# HDMI.net
KiCad netlist of a schematic drawn in Altium Designer
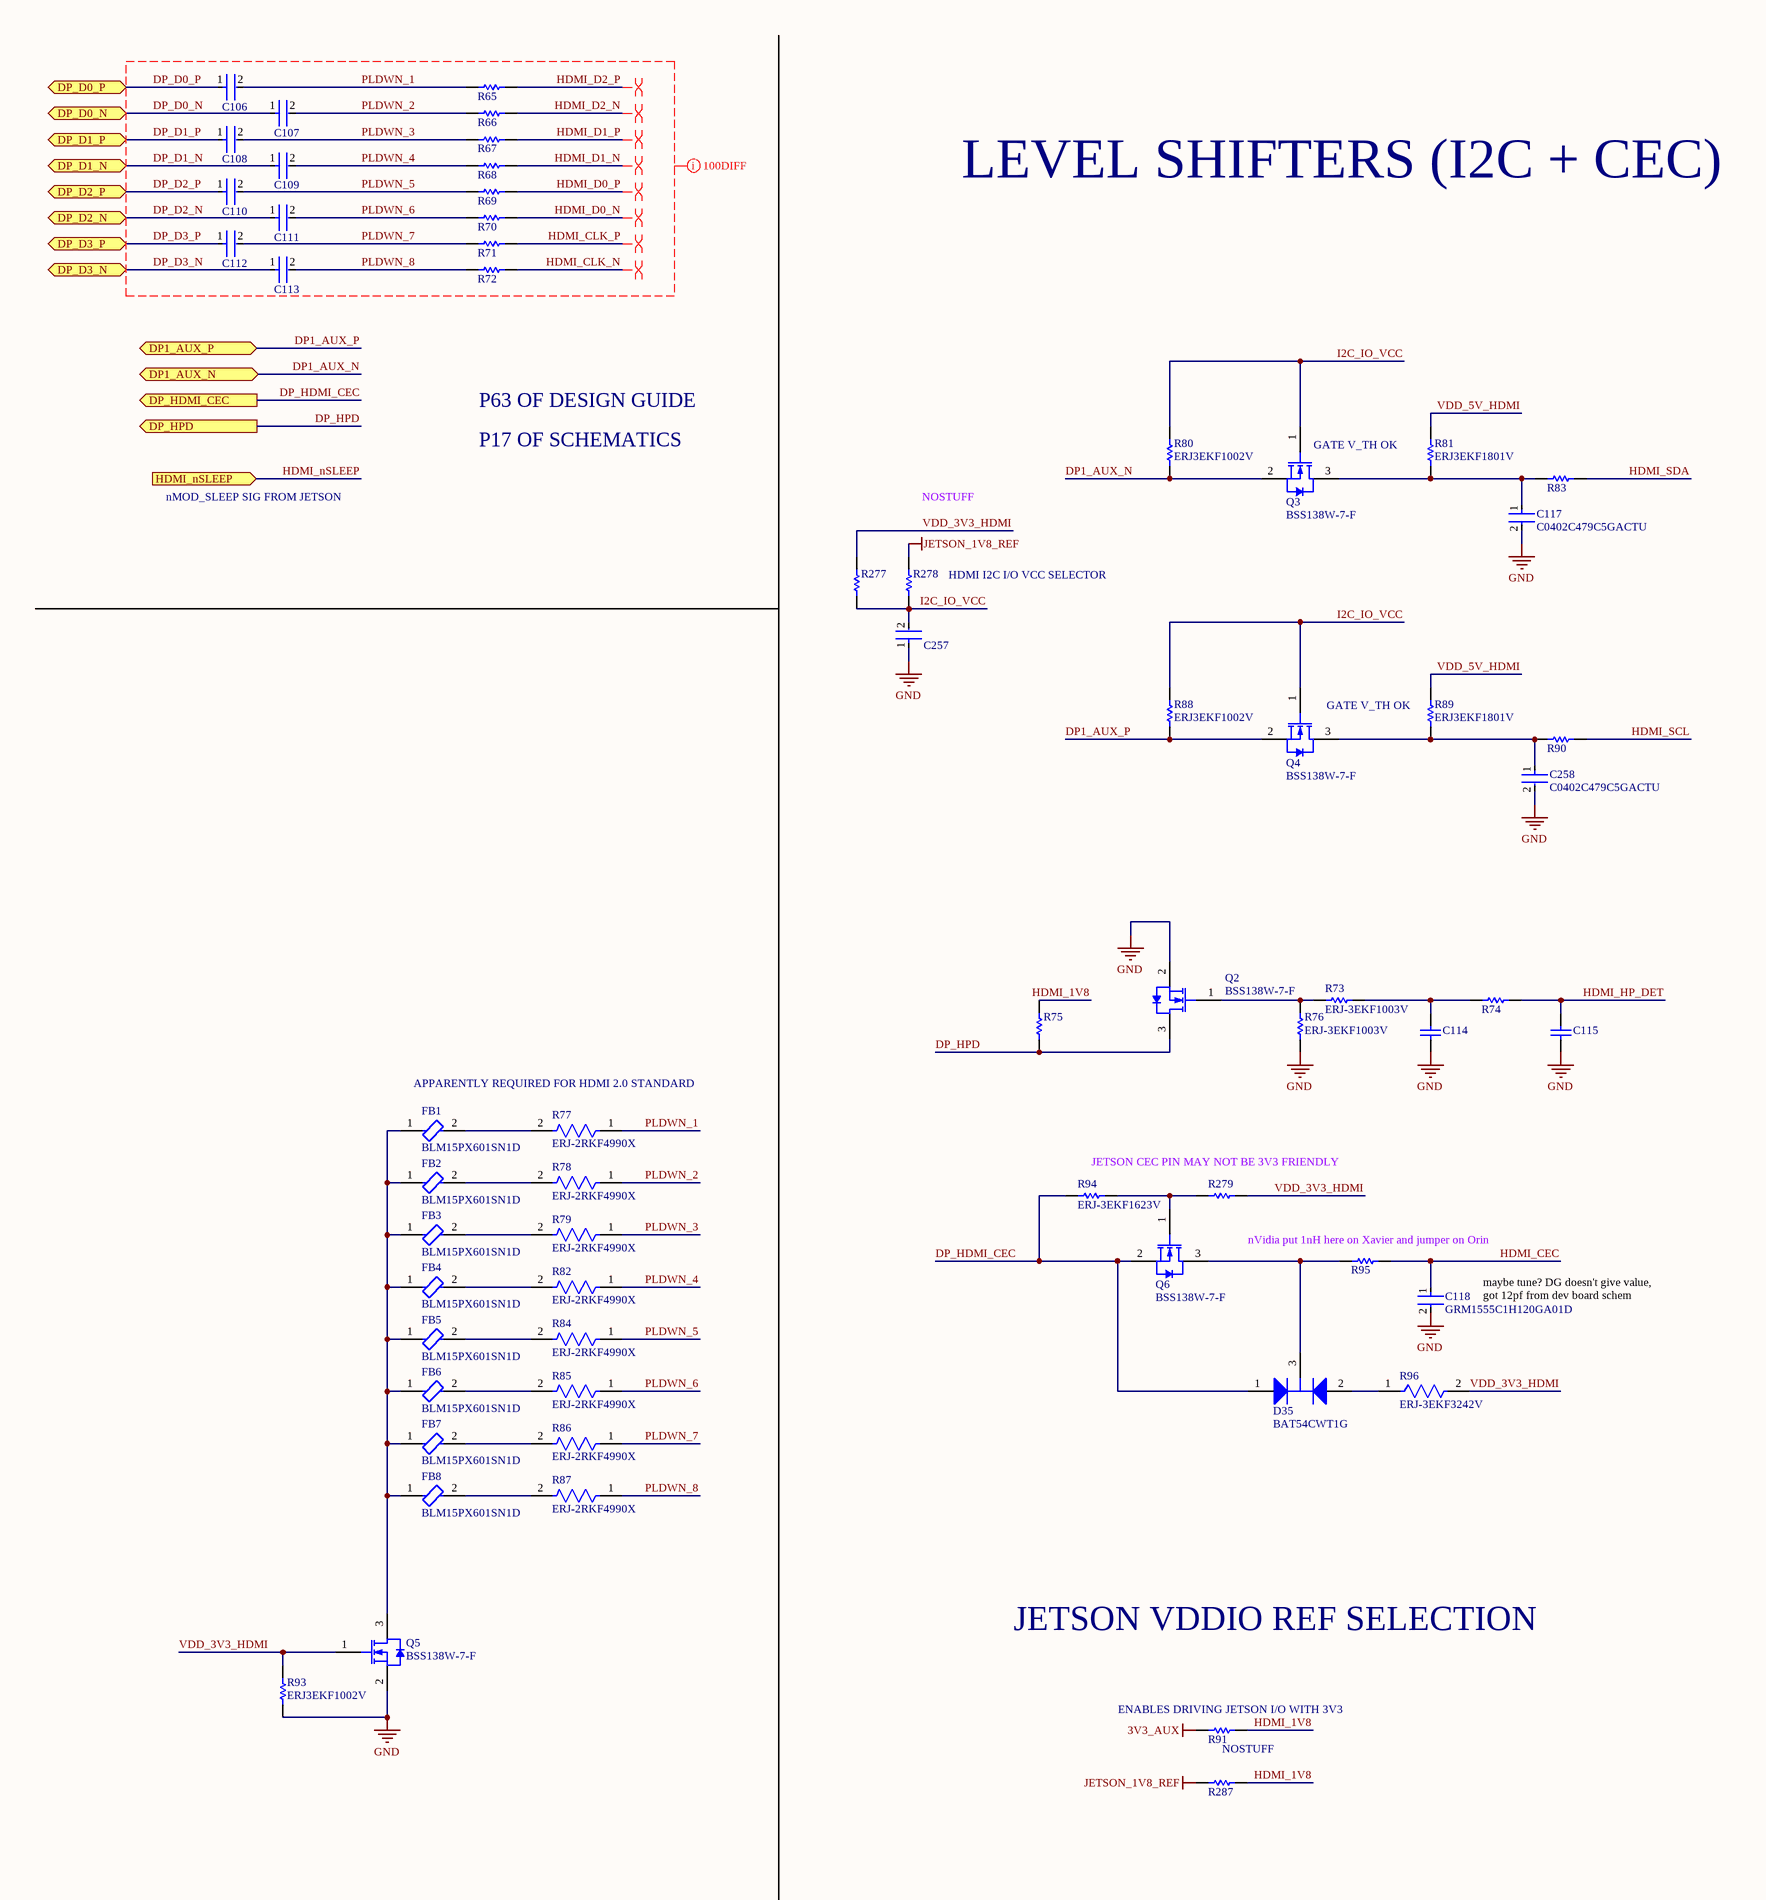
[diagram p0: HDMI.SchDoc, left]
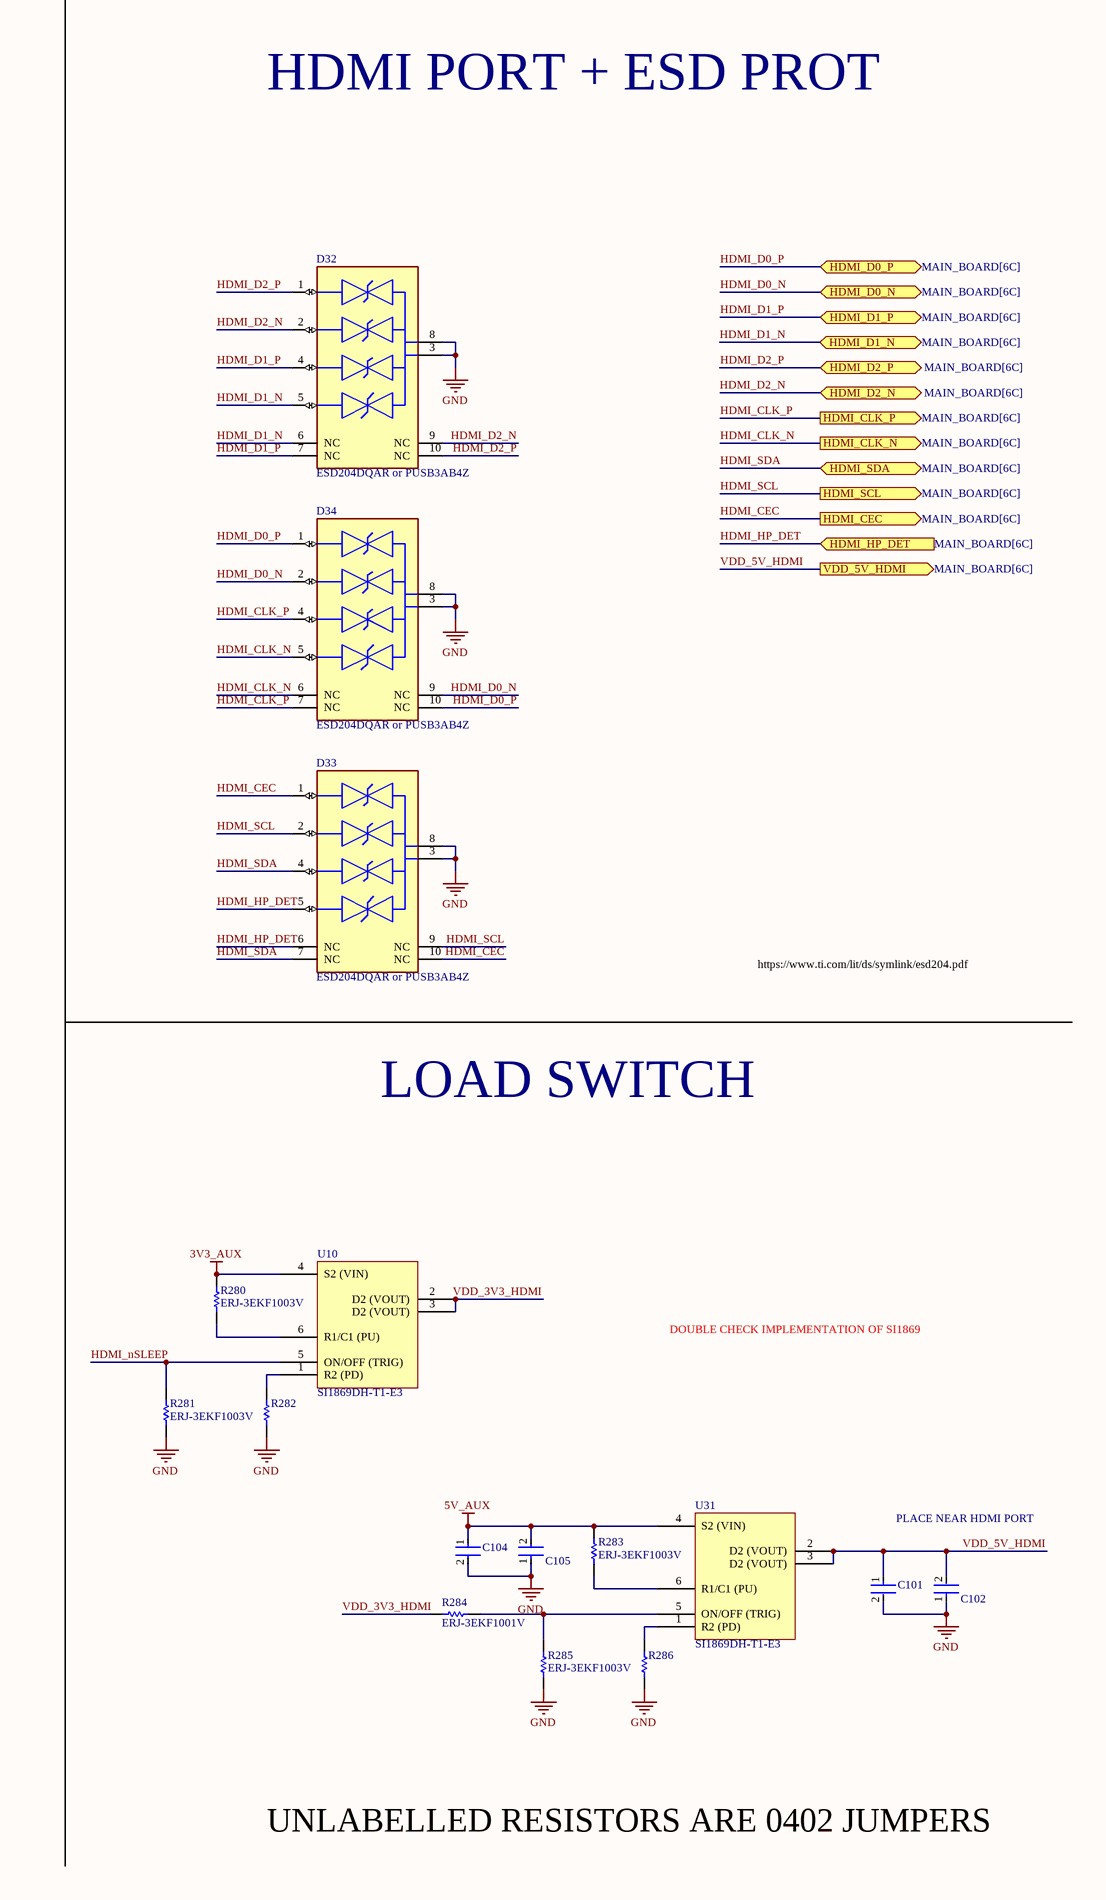
[diagram p1: HDMI.SchDoc, right]

(export (version "E")
  (design (tool "Eeschema 10.0.6"))
  (components
    (comp (ref "C101")
      (value "GRM188R60J106ME47D")
      (footprint "FP-GRM188-0_1-e0_2_0_55-IPC_A")
      (description "Chip Multilayer Ceramic Capacitors for General Purpose, 0603, 10uF, X5R, 15%, 20%, 6.3V")
      (fields (field (name "VOLTAGE") "6.3V") (field (name "TOLERANCE") "20%"))
      (libsource (lib "Altium Content Vault") (part "02cd4be3c70576c341d710602a673aa"))
    )
    (comp (ref "C102")
      (value "C1005X7R1H104K050BB")
      (footprint "FP-C1005-050-0_05-IPC_C")
      (description "Multilayer Ceramic Capacitors 100nF ±10% 50V X7R SMD 0402")
      (fields (field (name "VOLTAGE") "50V") (field (name "TOLERANCE") "10%"))
      (libsource (lib "Altium Content Vault") (part "b4654b650e69147ec39a6b967a45e02"))
    )
    (comp (ref "C104")
      (value "GRM188R60J106ME47D")
      (footprint "FP-GRM188-0_1-e0_2_0_55-IPC_A")
      (description "Chip Multilayer Ceramic Capacitors for General Purpose, 0603, 10uF, X5R, 15%, 20%, 6.3V")
      (fields (field (name "VOLTAGE") "6.3V") (field (name "TOLERANCE") "20%"))
      (libsource (lib "Altium Content Vault") (part "02cd4be3c70576c341d710602a673aa"))
    )
    (comp (ref "C105")
      (value "C1005X7R1H104K050BB")
      (footprint "FP-C1005-050-0_05-IPC_C")
      (description "Multilayer Ceramic Capacitors 100nF ±10% 50V X7R SMD 0402")
      (fields (field (name "VOLTAGE") "50V") (field (name "TOLERANCE") "10%"))
      (libsource (lib "Altium Content Vault") (part "b4654b650e69147ec39a6b967a45e02"))
    )
    (comp (ref "C106")
      (value "C1005X7R1H104K050BB")
      (footprint "FP-C1005-050-0_05-IPC_C")
      (description "Multilayer Ceramic Capacitors 100nF ±10% 50V X7R SMD 0402")
      (fields (field (name "VOLTAGE") "50V") (field (name "TOLERANCE") "10%"))
      (libsource (lib "Altium Content Vault") (part "b4654b650e69147ec39a6b967a45e02"))
    )
    (comp (ref "C107")
      (value "C1005X7R1H104K050BB")
      (footprint "FP-C1005-050-0_05-IPC_C")
      (description "Multilayer Ceramic Capacitors 100nF ±10% 50V X7R SMD 0402")
      (fields (field (name "VOLTAGE") "50V") (field (name "TOLERANCE") "10%"))
      (libsource (lib "Altium Content Vault") (part "b4654b650e69147ec39a6b967a45e02"))
    )
    (comp (ref "C108")
      (value "C1005X7R1H104K050BB")
      (footprint "FP-C1005-050-0_05-IPC_C")
      (description "Multilayer Ceramic Capacitors 100nF ±10% 50V X7R SMD 0402")
      (fields (field (name "VOLTAGE") "50V") (field (name "TOLERANCE") "10%"))
      (libsource (lib "Altium Content Vault") (part "b4654b650e69147ec39a6b967a45e02"))
    )
    (comp (ref "C109")
      (value "C1005X7R1H104K050BB")
      (footprint "FP-C1005-050-0_05-IPC_C")
      (description "Multilayer Ceramic Capacitors 100nF ±10% 50V X7R SMD 0402")
      (fields (field (name "VOLTAGE") "50V") (field (name "TOLERANCE") "10%"))
      (libsource (lib "Altium Content Vault") (part "b4654b650e69147ec39a6b967a45e02"))
    )
    (comp (ref "C110")
      (value "C1005X7R1H104K050BB")
      (footprint "FP-C1005-050-0_05-IPC_C")
      (description "Multilayer Ceramic Capacitors 100nF ±10% 50V X7R SMD 0402")
      (fields (field (name "VOLTAGE") "50V") (field (name "TOLERANCE") "10%"))
      (libsource (lib "Altium Content Vault") (part "b4654b650e69147ec39a6b967a45e02"))
    )
    (comp (ref "C111")
      (value "C1005X7R1H104K050BB")
      (footprint "FP-C1005-050-0_05-IPC_C")
      (description "Multilayer Ceramic Capacitors 100nF ±10% 50V X7R SMD 0402")
      (fields (field (name "VOLTAGE") "50V") (field (name "TOLERANCE") "10%"))
      (libsource (lib "Altium Content Vault") (part "b4654b650e69147ec39a6b967a45e02"))
    )
    (comp (ref "C112")
      (value "C1005X7R1H104K050BB")
      (footprint "FP-C1005-050-0_05-IPC_C")
      (description "Multilayer Ceramic Capacitors 100nF ±10% 50V X7R SMD 0402")
      (fields (field (name "VOLTAGE") "50V") (field (name "TOLERANCE") "10%"))
      (libsource (lib "Altium Content Vault") (part "b4654b650e69147ec39a6b967a45e02"))
    )
    (comp (ref "C113")
      (value "C1005X7R1H104K050BB")
      (footprint "FP-C1005-050-0_05-IPC_C")
      (description "Multilayer Ceramic Capacitors 100nF ±10% 50V X7R SMD 0402")
      (fields (field (name "VOLTAGE") "50V") (field (name "TOLERANCE") "10%"))
      (libsource (lib "Altium Content Vault") (part "b4654b650e69147ec39a6b967a45e02"))
    )
    (comp (ref "C114")
      (value "C0402C221K5RAC7867")
      (footprint "CAPC1005X60X30NL05T10")
      (fields (field (name "MANUFACTURER") "Kemet"))
      (libsource (lib "Altium Content Vault") (part "CAP"))
    )
    (comp (ref "C115")
      (value "C0402C221K5RAC7867")
      (footprint "CAPC1005X60X30NL05T10")
      (fields (field (name "MANUFACTURER") "Kemet"))
      (libsource (lib "Altium Content Vault") (part "CAP"))
    )
    (comp (ref "C117")
      (value "C0402C479C5GACTU")
      (footprint "FP-C0402-BB-MFG")
      (description "CAP CER 4.7PF 50V NP0 0402")
      (fields
        (field (name "TOLERANCE") "0.25 pF")
        (field (name "OCTOPART") "https://octopart.com/c0402c479c5gactu-kemet-9144199")
      )
      (libsource (lib "Altium Content Vault") (part "b4654b650e69147ec39a6b967a45e02"))
    )
    (comp (ref "C118")
      (value "GRM1555C1H120GA01D")
      (footprint "FP-GRM155-0_05-MFG")
      (description "CAP CER 12PF 50V C0G/NP0 0402")
      (fields (field (name "TOLERANCE") "2%") (field (name "VOLTAGE") "50V"))
      (libsource (lib "Altium Content Vault") (part "b4654b650e69147ec39a6b967a45e02"))
    )
    (comp (ref "C257")
      (value "C1005X7R1H104K050BB")
      (footprint "FP-C1005-050-0_05-IPC_C")
      (description "Multilayer Ceramic Capacitors 100nF ±10% 50V X7R SMD 0402")
      (fields (field (name "VOLTAGE") "50V") (field (name "TOLERANCE") "10%"))
      (libsource (lib "Altium Content Vault") (part "b4654b650e69147ec39a6b967a45e02"))
    )
    (comp (ref "C258")
      (value "C0402C479C5GACTU")
      (footprint "FP-C0402-BB-MFG")
      (description "CAP CER 4.7PF 50V NP0 0402")
      (fields
        (field (name "TOLERANCE") "0.25 pF")
        (field (name "OCTOPART") "https://octopart.com/c0402c479c5gactu-kemet-9144199")
      )
      (libsource (lib "Altium Content Vault") (part "b4654b650e69147ec39a6b967a45e02"))
    )
    (comp (ref "D32")
      (value "ESD204DQAR or PUSB3AB4Z")
      (footprint "FP-DQA0010A-MFG")
      (description "4-CHANNEL LOW-CAPACITANCE SURGE")
      (fields
        (field (name "MANUFACTURER") "Texas Instruments")
        (field (name "OCTOPART") "https://octopart.com/esd204dqar-texas+instruments-89917476")
      )
      (libsource (lib "Altium Content Vault") (part "1465e58c1818c7767b55926832f0bf5"))
    )
    (comp (ref "D33")
      (value "ESD204DQAR or PUSB3AB4Z")
      (footprint "FP-DQA0010A-MFG")
      (description "4-CHANNEL LOW-CAPACITANCE SURGE")
      (fields
        (field (name "MANUFACTURER") "Texas Instruments")
        (field (name "OCTOPART") "https://octopart.com/esd204dqar-texas+instruments-89917476")
      )
      (libsource (lib "Altium Content Vault") (part "1465e58c1818c7767b55926832f0bf5"))
    )
    (comp (ref "D34")
      (value "ESD204DQAR or PUSB3AB4Z")
      (footprint "FP-DQA0010A-MFG")
      (description "4-CHANNEL LOW-CAPACITANCE SURGE")
      (fields
        (field (name "MANUFACTURER") "Texas Instruments")
        (field (name "OCTOPART") "https://octopart.com/esd204dqar-texas+instruments-89917476")
      )
      (libsource (lib "Altium Content Vault") (part "1465e58c1818c7767b55926832f0bf5"))
    )
    (comp (ref "D35")
      (value "BAT54CWT1G")
      (footprint "ONSC-SOT-323-3-419-04_V")
      (description "Dual Series Cathode Schottky Barrier Diodes, 3-Pin SOT-323, Pb-Free, Tape and Reel")
      (fields (field (name "MANUFACTURER") "On Semiconductor"))
      (libsource (lib "Altium Content Vault") (part "ONSC-D-A1A2K3-3"))
    )
    (comp (ref "FB1")
      (value "BLM15PX601SN1D")
      (footprint "FP-BLM15-0_05-MFG")
      (description "Chip Ferrite Bead, 0402, 600Ω @ 100MHz, 0.23Ω, 25%, 900mA")
      (fields (field (name "TOLERANCE") "25%"))
      (libsource (lib "Altium Content Vault") (part "5f30dd21d616792df468990f7003faa"))
    )
    (comp (ref "FB2")
      (value "BLM15PX601SN1D")
      (footprint "FP-BLM15-0_05-MFG")
      (description "Chip Ferrite Bead, 0402, 600Ω @ 100MHz, 0.23Ω, 25%, 900mA")
      (fields (field (name "TOLERANCE") "25%"))
      (libsource (lib "Altium Content Vault") (part "5f30dd21d616792df468990f7003faa"))
    )
    (comp (ref "FB3")
      (value "BLM15PX601SN1D")
      (footprint "FP-BLM15-0_05-MFG")
      (description "Chip Ferrite Bead, 0402, 600Ω @ 100MHz, 0.23Ω, 25%, 900mA")
      (fields (field (name "TOLERANCE") "25%"))
      (libsource (lib "Altium Content Vault") (part "5f30dd21d616792df468990f7003faa"))
    )
    (comp (ref "FB4")
      (value "BLM15PX601SN1D")
      (footprint "FP-BLM15-0_05-MFG")
      (description "Chip Ferrite Bead, 0402, 600Ω @ 100MHz, 0.23Ω, 25%, 900mA")
      (fields (field (name "TOLERANCE") "25%"))
      (libsource (lib "Altium Content Vault") (part "5f30dd21d616792df468990f7003faa"))
    )
    (comp (ref "FB5")
      (value "BLM15PX601SN1D")
      (footprint "FP-BLM15-0_05-MFG")
      (description "Chip Ferrite Bead, 0402, 600Ω @ 100MHz, 0.23Ω, 25%, 900mA")
      (fields (field (name "TOLERANCE") "25%"))
      (libsource (lib "Altium Content Vault") (part "5f30dd21d616792df468990f7003faa"))
    )
    (comp (ref "FB6")
      (value "BLM15PX601SN1D")
      (footprint "FP-BLM15-0_05-MFG")
      (description "Chip Ferrite Bead, 0402, 600Ω @ 100MHz, 0.23Ω, 25%, 900mA")
      (fields (field (name "TOLERANCE") "25%"))
      (libsource (lib "Altium Content Vault") (part "5f30dd21d616792df468990f7003faa"))
    )
    (comp (ref "FB7")
      (value "BLM15PX601SN1D")
      (footprint "FP-BLM15-0_05-MFG")
      (description "Chip Ferrite Bead, 0402, 600Ω @ 100MHz, 0.23Ω, 25%, 900mA")
      (fields (field (name "TOLERANCE") "25%"))
      (libsource (lib "Altium Content Vault") (part "5f30dd21d616792df468990f7003faa"))
    )
    (comp (ref "FB8")
      (value "BLM15PX601SN1D")
      (footprint "FP-BLM15-0_05-MFG")
      (description "Chip Ferrite Bead, 0402, 600Ω @ 100MHz, 0.23Ω, 25%, 900mA")
      (fields (field (name "TOLERANCE") "25%"))
      (libsource (lib "Altium Content Vault") (part "5f30dd21d616792df468990f7003faa"))
    )
    (comp (ref "Q2")
      (value "BSS138W-7-F")
      (footprint "DIOD-SOT323-3_V")
      (fields (field (name "MANUFACTURER") "DiodesIncorporated"))
      (libsource (lib "Altium Content Vault") (part "NEMOS-GSD-3"))
    )
    (comp (ref "Q3")
      (value "BSS138W-7-F")
      (footprint "DIOD-SOT323-3_V")
      (fields (field (name "MANUFACTURER") "DiodesIncorporated"))
      (libsource (lib "Altium Content Vault") (part "NEMOS-GSD-3"))
    )
    (comp (ref "Q4")
      (value "BSS138W-7-F")
      (footprint "DIOD-SOT323-3_V")
      (fields (field (name "MANUFACTURER") "DiodesIncorporated"))
      (libsource (lib "Altium Content Vault") (part "NEMOS-GSD-3"))
    )
    (comp (ref "Q5")
      (value "BSS138W-7-F")
      (footprint "DIOD-SOT323-3_V")
      (fields (field (name "MANUFACTURER") "DiodesIncorporated"))
      (libsource (lib "Altium Content Vault") (part "NEMOS-GSD-3"))
    )
    (comp (ref "Q6")
      (value "BSS138W-7-F")
      (footprint "DIOD-SOT323-3_V")
      (fields (field (name "MANUFACTURER") "DiodesIncorporated"))
      (libsource (lib "Altium Content Vault") (part "NEMOS-GSD-3"))
    )
    (comp (ref "R65")
      (value "0402 JUMPER")
      (footprint "RESC1005X40X25ML05T05")
      (description "READ THE NAME")
      (libsource (lib "Space Concordia") (part "CMP-009-00206-2"))
    )
    (comp (ref "R66")
      (value "0402 JUMPER")
      (footprint "RESC1005X40X25ML05T05")
      (description "READ THE NAME")
      (libsource (lib "Space Concordia") (part "CMP-009-00206-2"))
    )
    (comp (ref "R67")
      (value "0402 JUMPER")
      (footprint "RESC1005X40X25ML05T05")
      (description "READ THE NAME")
      (libsource (lib "Space Concordia") (part "CMP-009-00206-2"))
    )
    (comp (ref "R68")
      (value "0402 JUMPER")
      (footprint "RESC1005X40X25ML05T05")
      (description "READ THE NAME")
      (libsource (lib "Space Concordia") (part "CMP-009-00206-2"))
    )
    (comp (ref "R69")
      (value "0402 JUMPER")
      (footprint "RESC1005X40X25ML05T05")
      (description "READ THE NAME")
      (libsource (lib "Space Concordia") (part "CMP-009-00206-2"))
    )
    (comp (ref "R70")
      (value "0402 JUMPER")
      (footprint "RESC1005X40X25ML05T05")
      (description "READ THE NAME")
      (libsource (lib "Space Concordia") (part "CMP-009-00206-2"))
    )
    (comp (ref "R71")
      (value "0402 JUMPER")
      (footprint "RESC1005X40X25ML05T05")
      (description "READ THE NAME")
      (libsource (lib "Space Concordia") (part "CMP-009-00206-2"))
    )
    (comp (ref "R72")
      (value "0402 JUMPER")
      (footprint "RESC1005X40X25ML05T05")
      (description "READ THE NAME")
      (libsource (lib "Space Concordia") (part "CMP-009-00206-2"))
    )
    (comp (ref "R73")
      (value "ERJ-3EKF1003V")
      (footprint "RESC1608X55X30ML15T15")
      (fields (field (name "MANUFACTURER") "Panasonic"))
      (libsource (lib "Altium Content Vault") (part "RES"))
    )
    (comp (ref "R74")
      (value "0402 JUMPER")
      (footprint "RESC1005X40X25ML05T05")
      (description "READ THE NAME")
      (libsource (lib "Space Concordia") (part "CMP-009-00206-2"))
    )
    (comp (ref "R75")
      (value "ERJ3EKF1002V")
      (footprint "RESC1609X55X30LL15T15")
      (description "Chip Resistor, 10 KOhm, +/- 1%, 0.1 W, -55 to 155 degC, 0603 (1608 Metric), RoHS, Tape and Reel")
      (fields (field (name "TOLERANCE") "1%") (field (name "MANUFACTURER") "Panasonic"))
      (libsource (lib "Altium Content Vault") (part "RES-2"))
    )
    (comp (ref "R76")
      (value "ERJ-3EKF1003V")
      (footprint "RESC1608X55X30ML15T15")
      (fields (field (name "MANUFACTURER") "Panasonic"))
      (libsource (lib "Altium Content Vault") (part "RES"))
    )
    (comp (ref "R77")
      (value "ERJ-2RKF4990X")
      (footprint "FP-ERJ2RK-MFG")
      (description "RES SMD 499 OHM 1% 1/10W 0402")
      (fields (field (name "TOLERANCE") "1%"))
      (libsource (lib "Altium Content Vault") (part "1029c3af85768c4190bb7ad29bc67b5"))
    )
    (comp (ref "R78")
      (value "ERJ-2RKF4990X")
      (footprint "FP-ERJ2RK-MFG")
      (description "RES SMD 499 OHM 1% 1/10W 0402")
      (fields (field (name "TOLERANCE") "1%"))
      (libsource (lib "Altium Content Vault") (part "1029c3af85768c4190bb7ad29bc67b5"))
    )
    (comp (ref "R79")
      (value "ERJ-2RKF4990X")
      (footprint "FP-ERJ2RK-MFG")
      (description "RES SMD 499 OHM 1% 1/10W 0402")
      (fields (field (name "TOLERANCE") "1%"))
      (libsource (lib "Altium Content Vault") (part "1029c3af85768c4190bb7ad29bc67b5"))
    )
    (comp (ref "R80")
      (value "ERJ3EKF1002V")
      (footprint "RESC1609X55X30LL15T15")
      (description "Chip Resistor, 10 KOhm, +/- 1%, 0.1 W, -55 to 155 degC, 0603 (1608 Metric), RoHS, Tape and Reel")
      (fields (field (name "TOLERANCE") "1%") (field (name "MANUFACTURER") "Panasonic"))
      (libsource (lib "Altium Content Vault") (part "RES-2"))
    )
    (comp (ref "R81")
      (value "ERJ3EKF1801V")
      (footprint "RESC1608X55X30LL15T15")
      (description "MODIFIED P/N")
      (fields (field (name "MANUFACTURER") "Panasonic") (field (name "PART NUMBER") "ERJ3EKF2701V"))
      (libsource (lib "Altium Content Vault") (part "RES"))
    )
    (comp (ref "R82")
      (value "ERJ-2RKF4990X")
      (footprint "FP-ERJ2RK-MFG")
      (description "RES SMD 499 OHM 1% 1/10W 0402")
      (fields (field (name "TOLERANCE") "1%"))
      (libsource (lib "Altium Content Vault") (part "1029c3af85768c4190bb7ad29bc67b5"))
    )
    (comp (ref "R83")
      (value "0402 JUMPER")
      (footprint "RESC1005X40X25ML05T05")
      (description "READ THE NAME")
      (libsource (lib "Space Concordia") (part "CMP-009-00206-2"))
    )
    (comp (ref "R84")
      (value "ERJ-2RKF4990X")
      (footprint "FP-ERJ2RK-MFG")
      (description "RES SMD 499 OHM 1% 1/10W 0402")
      (fields (field (name "TOLERANCE") "1%"))
      (libsource (lib "Altium Content Vault") (part "1029c3af85768c4190bb7ad29bc67b5"))
    )
    (comp (ref "R85")
      (value "ERJ-2RKF4990X")
      (footprint "FP-ERJ2RK-MFG")
      (description "RES SMD 499 OHM 1% 1/10W 0402")
      (fields (field (name "TOLERANCE") "1%"))
      (libsource (lib "Altium Content Vault") (part "1029c3af85768c4190bb7ad29bc67b5"))
    )
    (comp (ref "R86")
      (value "ERJ-2RKF4990X")
      (footprint "FP-ERJ2RK-MFG")
      (description "RES SMD 499 OHM 1% 1/10W 0402")
      (fields (field (name "TOLERANCE") "1%"))
      (libsource (lib "Altium Content Vault") (part "1029c3af85768c4190bb7ad29bc67b5"))
    )
    (comp (ref "R87")
      (value "ERJ-2RKF4990X")
      (footprint "FP-ERJ2RK-MFG")
      (description "RES SMD 499 OHM 1% 1/10W 0402")
      (fields (field (name "TOLERANCE") "1%"))
      (libsource (lib "Altium Content Vault") (part "1029c3af85768c4190bb7ad29bc67b5"))
    )
    (comp (ref "R88")
      (value "ERJ3EKF1002V")
      (footprint "RESC1609X55X30LL15T15")
      (description "Chip Resistor, 10 KOhm, +/- 1%, 0.1 W, -55 to 155 degC, 0603 (1608 Metric), RoHS, Tape and Reel")
      (fields (field (name "TOLERANCE") "1%") (field (name "MANUFACTURER") "Panasonic"))
      (libsource (lib "Altium Content Vault") (part "RES-2"))
    )
    (comp (ref "R89")
      (value "ERJ3EKF1801V")
      (footprint "RESC1608X55X30LL15T15")
      (description "MODIFIED P/N")
      (fields (field (name "MANUFACTURER") "Panasonic") (field (name "PART NUMBER") "ERJ3EKF2701V"))
      (libsource (lib "Altium Content Vault") (part "RES"))
    )
    (comp (ref "R90")
      (value "0402 JUMPER")
      (footprint "RESC1005X40X25ML05T05")
      (description "READ THE NAME")
      (libsource (lib "Space Concordia") (part "CMP-009-00206-2"))
    )
    (comp (ref "R91")
      (value "0402 JUMPER")
      (footprint "RESC1005X40X25ML05T05")
      (description "READ THE NAME")
      (libsource (lib "Space Concordia") (part "CMP-009-00206-2"))
    )
    (comp (ref "R93")
      (value "ERJ3EKF1002V")
      (footprint "RESC1609X55X30LL15T15")
      (description "Chip Resistor, 10 KOhm, +/- 1%, 0.1 W, -55 to 155 degC, 0603 (1608 Metric), RoHS, Tape and Reel")
      (fields (field (name "TOLERANCE") "1%") (field (name "MANUFACTURER") "Panasonic"))
      (libsource (lib "Altium Content Vault") (part "RES-2"))
    )
    (comp (ref "R94")
      (value "ERJ-3EKF1623V")
      (footprint "RESC1608X55X30ML15T15")
      (fields (field (name "MANUFACTURER") "Panasonic"))
      (libsource (lib "Altium Content Vault") (part "RES"))
    )
    (comp (ref "R95")
      (value "0402 JUMPER")
      (footprint "RESC1005X40X25ML05T05")
      (description "READ THE NAME")
      (libsource (lib "Space Concordia") (part "CMP-009-00206-2"))
    )
    (comp (ref "R96")
      (value "ERJ-3EKF3242V")
      (footprint "FP-ERJ3EK-MFG")
      (description "RES SMD 32.4K OHM 1% 1/10W 0603")
      (fields (field (name "TOLERANCE") "1%"))
      (libsource (lib "Altium Content Vault") (part "1029c3af85768c4190bb7ad29bc67b5"))
    )
    (comp (ref "R277")
      (value "0402 JUMPER")
      (footprint "RESC1005X40X25ML05T05")
      (description "READ THE NAME")
      (libsource (lib "Space Concordia") (part "CMP-009-00206-2"))
    )
    (comp (ref "R278")
      (value "0402 JUMPER")
      (footprint "RESC1005X40X25ML05T05")
      (description "READ THE NAME")
      (libsource (lib "Space Concordia") (part "CMP-009-00206-2"))
    )
    (comp (ref "R279")
      (value "0402 JUMPER")
      (footprint "RESC1005X40X25ML05T05")
      (description "READ THE NAME")
      (libsource (lib "Space Concordia") (part "CMP-009-00206-2"))
    )
    (comp (ref "R280")
      (value "ERJ-3EKF1003V")
      (footprint "RESC1608X55X30ML15T15")
      (fields (field (name "MANUFACTURER") "Panasonic"))
      (libsource (lib "Altium Content Vault") (part "RES"))
    )
    (comp (ref "R281")
      (value "ERJ-3EKF1003V")
      (footprint "RESC1608X55X30ML15T15")
      (fields (field (name "MANUFACTURER") "Panasonic"))
      (libsource (lib "Altium Content Vault") (part "RES"))
    )
    (comp (ref "R282")
      (value "0402 JUMPER")
      (footprint "RESC1005X40X25ML05T05")
      (description "READ THE NAME")
      (libsource (lib "Space Concordia") (part "CMP-009-00206-2"))
    )
    (comp (ref "R283")
      (value "ERJ-3EKF1003V")
      (footprint "RESC1608X55X30ML15T15")
      (fields (field (name "MANUFACTURER") "Panasonic"))
      (libsource (lib "Altium Content Vault") (part "RES"))
    )
    (comp (ref "R284")
      (value "ERJ-3EKF1001V")
      (footprint "RESC1608X55X30LL15T15")
      (fields (field (name "MANUFACTURER") "Panasonic"))
      (libsource (lib "Altium Content Vault") (part "RES"))
    )
    (comp (ref "R285")
      (value "ERJ-3EKF1003V")
      (footprint "RESC1608X55X30ML15T15")
      (fields (field (name "MANUFACTURER") "Panasonic"))
      (libsource (lib "Altium Content Vault") (part "RES"))
    )
    (comp (ref "R286")
      (value "0402 JUMPER")
      (footprint "RESC1005X40X25ML05T05")
      (description "READ THE NAME")
      (libsource (lib "Space Concordia") (part "CMP-009-00206-2"))
    )
    (comp (ref "R287")
      (value "0402 JUMPER")
      (footprint "RESC1005X40X25ML05T05")
      (description "READ THE NAME")
      (libsource (lib "Space Concordia") (part "CMP-009-00206-2"))
    )
    (comp (ref "U10")
      (value "SI1869DH-T1-E3")
      (footprint "SOT65P242X110-6N")
      (description "Power Supply Support Circuit, Adjustable, 1 Channel, PDSO6")
      (libsource (lib "Space Concordia") (part "SI1869DH-T1-E3"))
    )
    (comp (ref "U31")
      (value "SI1869DH-T1-E3")
      (footprint "SOT65P242X110-6N")
      (description "Power Supply Support Circuit, Adjustable, 1 Channel, PDSO6")
      (libsource (lib "Space Concordia") (part "SI1869DH-T1-E3"))
    )
  )
  (nets
    (net (code "1") (name "/DP1_AUX_N") (class "Default")
      (node (ref "Q3") (pin "2") (pinfunction "S_2") (pintype "passive"))
      (node (ref "R80") (pin "1") (pinfunction "1_1") (pintype "passive"))
    )
    (net (code "2") (name "/DP1_AUX_P") (class "Default")
      (node (ref "Q4") (pin "2") (pinfunction "S_2") (pintype "passive"))
      (node (ref "R88") (pin "1") (pinfunction "1_1") (pintype "passive"))
    )
    (net (code "3") (name "/DP_D0_N") (class "Default")
      (node (ref "C107") (pin "1") (pinfunction "1_1") (pintype "passive"))
    )
    (net (code "4") (name "/DP_D0_P") (class "Default")
      (node (ref "C106") (pin "1") (pinfunction "1_1") (pintype "passive"))
    )
    (net (code "5") (name "/DP_D1_N") (class "Default")
      (node (ref "C109") (pin "1") (pinfunction "1_1") (pintype "passive"))
    )
    (net (code "6") (name "/DP_D1_P") (class "Default")
      (node (ref "C108") (pin "1") (pinfunction "1_1") (pintype "passive"))
    )
    (net (code "7") (name "/DP_D2_N") (class "Default")
      (node (ref "C111") (pin "1") (pinfunction "1_1") (pintype "passive"))
    )
    (net (code "8") (name "/DP_D2_P") (class "Default")
      (node (ref "C110") (pin "1") (pinfunction "1_1") (pintype "passive"))
    )
    (net (code "9") (name "/DP_D3_N") (class "Default")
      (node (ref "C113") (pin "1") (pinfunction "1_1") (pintype "passive"))
    )
    (net (code "10") (name "/DP_D3_P") (class "Default")
      (node (ref "C112") (pin "1") (pinfunction "1_1") (pintype "passive"))
    )
    (net (code "11") (name "/DP_HDMI_CEC") (class "Default")
      (node (ref "D35") (pin "1") (pinfunction "A1_1") (pintype "passive"))
      (node (ref "Q6") (pin "2") (pinfunction "S_2") (pintype "passive"))
      (node (ref "R94") (pin "1") (pinfunction "1_1") (pintype "passive"))
    )
    (net (code "12") (name "/DP_HPD") (class "Default")
      (node (ref "Q2") (pin "3") (pinfunction "D_3") (pintype "passive"))
      (node (ref "R75") (pin "1") (pinfunction "1_1") (pintype "passive"))
    )
    (net (code "13") (name "/HDMI_1V8") (class "Default")
      (node (ref "R287") (pin "2") (pinfunction "2_2") (pintype "passive"))
      (node (ref "R75") (pin "2") (pinfunction "2_2") (pintype "passive"))
      (node (ref "R91") (pin "2") (pinfunction "2_2") (pintype "passive"))
    )
    (net (code "14") (name "/HDMI_CEC") (class "Default")
      (node (ref "C118") (pin "1") (pinfunction "1_1") (pintype "passive"))
      (node (ref "D33") (pin "1") (pinfunction "IO1_1") (pintype "bidirectional"))
      (node (ref "D33") (pin "10") (pinfunction "NC_10") (pintype "passive"))
      (node (ref "R95") (pin "2") (pinfunction "2_2") (pintype "passive"))
    )
    (net (code "15") (name "/HDMI_CLK_N") (class "Default")
      (node (ref "D34") (pin "5") (pinfunction "IO4_5") (pintype "bidirectional"))
      (node (ref "D34") (pin "6") (pinfunction "NC_6") (pintype "passive"))
      (node (ref "R72") (pin "2") (pinfunction "2_2") (pintype "passive"))
    )
    (net (code "16") (name "/HDMI_CLK_P") (class "Default")
      (node (ref "D34") (pin "4") (pinfunction "IO3_4") (pintype "bidirectional"))
      (node (ref "D34") (pin "7") (pinfunction "NC_7") (pintype "passive"))
      (node (ref "R71") (pin "2") (pinfunction "2_2") (pintype "passive"))
    )
    (net (code "17") (name "/HDMI_D0_N") (class "Default")
      (node (ref "D34") (pin "2") (pinfunction "IO2_2") (pintype "bidirectional"))
      (node (ref "D34") (pin "9") (pinfunction "NC_9") (pintype "passive"))
      (node (ref "R70") (pin "2") (pinfunction "2_2") (pintype "passive"))
    )
    (net (code "18") (name "/HDMI_D0_P") (class "Default")
      (node (ref "D34") (pin "1") (pinfunction "IO1_1") (pintype "bidirectional"))
      (node (ref "D34") (pin "10") (pinfunction "NC_10") (pintype "passive"))
      (node (ref "R69") (pin "2") (pinfunction "2_2") (pintype "passive"))
    )
    (net (code "19") (name "/HDMI_D1_N") (class "Default")
      (node (ref "D32") (pin "5") (pinfunction "IO4_5") (pintype "bidirectional"))
      (node (ref "D32") (pin "6") (pinfunction "NC_6") (pintype "passive"))
      (node (ref "R68") (pin "2") (pinfunction "2_2") (pintype "passive"))
    )
    (net (code "20") (name "/HDMI_D1_P") (class "Default")
      (node (ref "D32") (pin "4") (pinfunction "IO3_4") (pintype "bidirectional"))
      (node (ref "D32") (pin "7") (pinfunction "NC_7") (pintype "passive"))
      (node (ref "R67") (pin "2") (pinfunction "2_2") (pintype "passive"))
    )
    (net (code "21") (name "/HDMI_D2_N") (class "Default")
      (node (ref "D32") (pin "2") (pinfunction "IO2_2") (pintype "bidirectional"))
      (node (ref "D32") (pin "9") (pinfunction "NC_9") (pintype "passive"))
      (node (ref "R66") (pin "2") (pinfunction "2_2") (pintype "passive"))
    )
    (net (code "22") (name "/HDMI_D2_P") (class "Default")
      (node (ref "D32") (pin "1") (pinfunction "IO1_1") (pintype "bidirectional"))
      (node (ref "D32") (pin "10") (pinfunction "NC_10") (pintype "passive"))
      (node (ref "R65") (pin "2") (pinfunction "2_2") (pintype "passive"))
    )
    (net (code "23") (name "/HDMI_HP_DET") (class "Default")
      (node (ref "C115") (pin "2") (pinfunction "2_2") (pintype "passive"))
      (node (ref "D33") (pin "5") (pinfunction "IO4_5") (pintype "bidirectional"))
      (node (ref "D33") (pin "6") (pinfunction "NC_6") (pintype "passive"))
      (node (ref "R74") (pin "2") (pinfunction "2_2") (pintype "passive"))
    )
    (net (code "24") (name "/HDMI_SCL") (class "Default")
      (node (ref "D33") (pin "2") (pinfunction "IO2_2") (pintype "bidirectional"))
      (node (ref "D33") (pin "9") (pinfunction "NC_9") (pintype "passive"))
      (node (ref "R90") (pin "2") (pinfunction "2_2") (pintype "passive"))
    )
    (net (code "25") (name "/HDMI_SDA") (class "Default")
      (node (ref "D33") (pin "4") (pinfunction "IO3_4") (pintype "bidirectional"))
      (node (ref "D33") (pin "7") (pinfunction "NC_7") (pintype "passive"))
      (node (ref "R83") (pin "2") (pinfunction "2_2") (pintype "passive"))
    )
    (net (code "26") (name "/HDMI_nSLEEP") (class "Default")
      (node (ref "R281") (pin "2") (pinfunction "2_2") (pintype "passive"))
      (node (ref "U10") (pin "5") (pinfunction "ON/OFF_(TRIG)_5") (pintype "passive"))
    )
    (net (code "27") (name "/I2C_IO_VCC") (class "Default")
      (node (ref "C257") (pin "2") (pinfunction "2_2") (pintype "passive"))
      (node (ref "Q3") (pin "1") (pinfunction "G_1") (pintype "passive"))
      (node (ref "Q4") (pin "1") (pinfunction "G_1") (pintype "passive"))
      (node (ref "R277") (pin "1") (pinfunction "1_1") (pintype "passive"))
      (node (ref "R278") (pin "1") (pinfunction "1_1") (pintype "passive"))
      (node (ref "R80") (pin "2") (pinfunction "2_2") (pintype "passive"))
      (node (ref "R88") (pin "2") (pinfunction "2_2") (pintype "passive"))
    )
    (net (code "28") (name "/PLDWN_1") (class "Default")
      (node (ref "C106") (pin "2") (pinfunction "2_2") (pintype "passive"))
      (node (ref "R65") (pin "1") (pinfunction "1_1") (pintype "passive"))
      (node (ref "R77") (pin "1") (pinfunction "1_1") (pintype "passive"))
    )
    (net (code "29") (name "/PLDWN_2") (class "Default")
      (node (ref "C107") (pin "2") (pinfunction "2_2") (pintype "passive"))
      (node (ref "R66") (pin "1") (pinfunction "1_1") (pintype "passive"))
      (node (ref "R78") (pin "1") (pinfunction "1_1") (pintype "passive"))
    )
    (net (code "30") (name "/PLDWN_3") (class "Default")
      (node (ref "C108") (pin "2") (pinfunction "2_2") (pintype "passive"))
      (node (ref "R67") (pin "1") (pinfunction "1_1") (pintype "passive"))
      (node (ref "R79") (pin "1") (pinfunction "1_1") (pintype "passive"))
    )
    (net (code "31") (name "/PLDWN_4") (class "Default")
      (node (ref "C109") (pin "2") (pinfunction "2_2") (pintype "passive"))
      (node (ref "R68") (pin "1") (pinfunction "1_1") (pintype "passive"))
      (node (ref "R82") (pin "1") (pinfunction "1_1") (pintype "passive"))
    )
    (net (code "32") (name "/PLDWN_5") (class "Default")
      (node (ref "C110") (pin "2") (pinfunction "2_2") (pintype "passive"))
      (node (ref "R69") (pin "1") (pinfunction "1_1") (pintype "passive"))
      (node (ref "R84") (pin "1") (pinfunction "1_1") (pintype "passive"))
    )
    (net (code "33") (name "/PLDWN_6") (class "Default")
      (node (ref "C111") (pin "2") (pinfunction "2_2") (pintype "passive"))
      (node (ref "R70") (pin "1") (pinfunction "1_1") (pintype "passive"))
      (node (ref "R85") (pin "1") (pinfunction "1_1") (pintype "passive"))
    )
    (net (code "34") (name "/PLDWN_7") (class "Default")
      (node (ref "C112") (pin "2") (pinfunction "2_2") (pintype "passive"))
      (node (ref "R71") (pin "1") (pinfunction "1_1") (pintype "passive"))
      (node (ref "R86") (pin "1") (pinfunction "1_1") (pintype "passive"))
    )
    (net (code "35") (name "/PLDWN_8") (class "Default")
      (node (ref "C113") (pin "2") (pinfunction "2_2") (pintype "passive"))
      (node (ref "R72") (pin "1") (pinfunction "1_1") (pintype "passive"))
      (node (ref "R87") (pin "1") (pinfunction "1_1") (pintype "passive"))
    )
    (net (code "36") (name "/VDD_3V3_HDMI") (class "Default")
      (node (ref "Q5") (pin "1") (pinfunction "G_1") (pintype "passive"))
      (node (ref "R277") (pin "2") (pinfunction "2_2") (pintype "passive"))
      (node (ref "R279") (pin "1") (pinfunction "1_1") (pintype "passive"))
      (node (ref "R284") (pin "1") (pinfunction "1_1") (pintype "passive"))
      (node (ref "R93") (pin "2") (pinfunction "2_2") (pintype "passive"))
      (node (ref "R96") (pin "2") (pinfunction "2_2") (pintype "passive"))
      (node (ref "U10") (pin "2") (pinfunction "D2_(VOUT)_2") (pintype "passive"))
      (node (ref "U10") (pin "3") (pinfunction "D2_(VOUT)_3") (pintype "passive"))
    )
    (net (code "37") (name "/VDD_5V_HDMI") (class "Default")
      (node (ref "C101") (pin "1") (pinfunction "1_1") (pintype "passive"))
      (node (ref "C102") (pin "2") (pinfunction "2_2") (pintype "passive"))
      (node (ref "R81") (pin "2") (pinfunction "2_2") (pintype "passive"))
      (node (ref "R89") (pin "2") (pinfunction "2_2") (pintype "passive"))
      (node (ref "U31") (pin "2") (pinfunction "D2_(VOUT)_2") (pintype "passive"))
      (node (ref "U31") (pin "3") (pinfunction "D2_(VOUT)_3") (pintype "passive"))
    )
    (net (code "38") (name "3V3_AUX") (class "Default")
      (node (ref "R280") (pin "2") (pinfunction "2_2") (pintype "passive"))
      (node (ref "R91") (pin "1") (pinfunction "1_1") (pintype "passive"))
      (node (ref "U10") (pin "4") (pinfunction "S2_(VIN)_4") (pintype "passive"))
    )
    (net (code "39") (name "5V_AUX") (class "Default")
      (node (ref "C104") (pin "1") (pinfunction "1_1") (pintype "passive"))
      (node (ref "C105") (pin "2") (pinfunction "2_2") (pintype "passive"))
      (node (ref "R283") (pin "2") (pinfunction "2_2") (pintype "passive"))
      (node (ref "U31") (pin "4") (pinfunction "S2_(VIN)_4") (pintype "passive"))
    )
    (net (code "40") (name "GND") (class "Default")
      (node (ref "C101") (pin "2") (pinfunction "2_2") (pintype "passive"))
      (node (ref "C102") (pin "1") (pinfunction "1_1") (pintype "passive"))
      (node (ref "C104") (pin "2") (pinfunction "2_2") (pintype "passive"))
      (node (ref "C105") (pin "1") (pinfunction "1_1") (pintype "passive"))
      (node (ref "C114") (pin "1") (pinfunction "1_1") (pintype "passive"))
      (node (ref "C115") (pin "1") (pinfunction "1_1") (pintype "passive"))
      (node (ref "C117") (pin "2") (pinfunction "2_2") (pintype "passive"))
      (node (ref "C118") (pin "2") (pinfunction "2_2") (pintype "passive"))
      (node (ref "C257") (pin "1") (pinfunction "1_1") (pintype "passive"))
      (node (ref "C258") (pin "2") (pinfunction "2_2") (pintype "passive"))
      (node (ref "D32") (pin "3") (pinfunction "GND_3") (pintype "power_in"))
      (node (ref "D32") (pin "8") (pinfunction "GND_8") (pintype "power_in"))
      (node (ref "D33") (pin "3") (pinfunction "GND_3") (pintype "power_in"))
      (node (ref "D33") (pin "8") (pinfunction "GND_8") (pintype "power_in"))
      (node (ref "D34") (pin "3") (pinfunction "GND_3") (pintype "power_in"))
      (node (ref "D34") (pin "8") (pinfunction "GND_8") (pintype "power_in"))
      (node (ref "Q2") (pin "2") (pinfunction "S_2") (pintype "passive"))
      (node (ref "Q5") (pin "2") (pinfunction "S_2") (pintype "passive"))
      (node (ref "R281") (pin "1") (pinfunction "1_1") (pintype "passive"))
      (node (ref "R282") (pin "2") (pinfunction "2_2") (pintype "passive"))
      (node (ref "R285") (pin "1") (pinfunction "1_1") (pintype "passive"))
      (node (ref "R286") (pin "2") (pinfunction "2_2") (pintype "passive"))
      (node (ref "R76") (pin "1") (pinfunction "1_1") (pintype "passive"))
      (node (ref "R93") (pin "1") (pinfunction "1_1") (pintype "passive"))
    )
    (net (code "41") (name "JETSON_1V8_REF") (class "Default")
      (node (ref "R278") (pin "2") (pinfunction "2_2") (pintype "passive"))
      (node (ref "R287") (pin "1") (pinfunction "1_1") (pintype "passive"))
    )
    (net (code "42") (name "Net-(C114-Pad2)") (class "Default")
      (node (ref "C114") (pin "2") (pinfunction "2_2") (pintype "passive"))
      (node (ref "R73") (pin "2") (pinfunction "2_2") (pintype "passive"))
      (node (ref "R74") (pin "1") (pinfunction "1_1") (pintype "passive"))
    )
    (net (code "43") (name "Net-(D35-A2)") (class "Default")
      (node (ref "D35") (pin "2") (pinfunction "A2_2") (pintype "passive"))
      (node (ref "R96") (pin "1") (pinfunction "1_1") (pintype "passive"))
    )
    (net (code "44") (name "Net-(D35-K)") (class "Default")
      (node (ref "D35") (pin "3") (pinfunction "K_3") (pintype "passive"))
      (node (ref "Q6") (pin "3") (pinfunction "D_3") (pintype "passive"))
      (node (ref "R95") (pin "1") (pinfunction "1_1") (pintype "passive"))
    )
    (net (code "45") (name "Net-(FB1-Pad2)") (class "Default")
      (node (ref "FB1") (pin "2") (pinfunction "2_2") (pintype "passive"))
      (node (ref "R77") (pin "2") (pinfunction "2_2") (pintype "passive"))
    )
    (net (code "46") (name "Net-(FB2-Pad2)") (class "Default")
      (node (ref "FB2") (pin "2") (pinfunction "2_2") (pintype "passive"))
      (node (ref "R78") (pin "2") (pinfunction "2_2") (pintype "passive"))
    )
    (net (code "47") (name "Net-(FB3-Pad2)") (class "Default")
      (node (ref "FB3") (pin "2") (pinfunction "2_2") (pintype "passive"))
      (node (ref "R79") (pin "2") (pinfunction "2_2") (pintype "passive"))
    )
    (net (code "48") (name "Net-(FB4-Pad2)") (class "Default")
      (node (ref "FB4") (pin "2") (pinfunction "2_2") (pintype "passive"))
      (node (ref "R82") (pin "2") (pinfunction "2_2") (pintype "passive"))
    )
    (net (code "49") (name "Net-(FB5-Pad2)") (class "Default")
      (node (ref "FB5") (pin "2") (pinfunction "2_2") (pintype "passive"))
      (node (ref "R84") (pin "2") (pinfunction "2_2") (pintype "passive"))
    )
    (net (code "50") (name "Net-(FB6-Pad2)") (class "Default")
      (node (ref "FB6") (pin "2") (pinfunction "2_2") (pintype "passive"))
      (node (ref "R85") (pin "2") (pinfunction "2_2") (pintype "passive"))
    )
    (net (code "51") (name "Net-(FB7-Pad2)") (class "Default")
      (node (ref "FB7") (pin "2") (pinfunction "2_2") (pintype "passive"))
      (node (ref "R86") (pin "2") (pinfunction "2_2") (pintype "passive"))
    )
    (net (code "52") (name "Net-(FB8-Pad2)") (class "Default")
      (node (ref "FB8") (pin "2") (pinfunction "2_2") (pintype "passive"))
      (node (ref "R87") (pin "2") (pinfunction "2_2") (pintype "passive"))
    )
    (net (code "53") (name "Net-(Q2-G)") (class "Default")
      (node (ref "Q2") (pin "1") (pinfunction "G_1") (pintype "passive"))
      (node (ref "R73") (pin "1") (pinfunction "1_1") (pintype "passive"))
      (node (ref "R76") (pin "2") (pinfunction "2_2") (pintype "passive"))
    )
    (net (code "54") (name "Net-(Q3-D)") (class "Default")
      (node (ref "C117") (pin "1") (pinfunction "1_1") (pintype "passive"))
      (node (ref "Q3") (pin "3") (pinfunction "D_3") (pintype "passive"))
      (node (ref "R81") (pin "1") (pinfunction "1_1") (pintype "passive"))
      (node (ref "R83") (pin "1") (pinfunction "1_1") (pintype "passive"))
    )
    (net (code "55") (name "Net-(Q4-D)") (class "Default")
      (node (ref "C258") (pin "1") (pinfunction "1_1") (pintype "passive"))
      (node (ref "Q4") (pin "3") (pinfunction "D_3") (pintype "passive"))
      (node (ref "R89") (pin "1") (pinfunction "1_1") (pintype "passive"))
      (node (ref "R90") (pin "1") (pinfunction "1_1") (pintype "passive"))
    )
    (net (code "56") (name "Net-(Q5-D)") (class "Default")
      (node (ref "FB1") (pin "1") (pinfunction "1_1") (pintype "passive"))
      (node (ref "FB2") (pin "1") (pinfunction "1_1") (pintype "passive"))
      (node (ref "FB3") (pin "1") (pinfunction "1_1") (pintype "passive"))
      (node (ref "FB4") (pin "1") (pinfunction "1_1") (pintype "passive"))
      (node (ref "FB5") (pin "1") (pinfunction "1_1") (pintype "passive"))
      (node (ref "FB6") (pin "1") (pinfunction "1_1") (pintype "passive"))
      (node (ref "FB7") (pin "1") (pinfunction "1_1") (pintype "passive"))
      (node (ref "FB8") (pin "1") (pinfunction "1_1") (pintype "passive"))
      (node (ref "Q5") (pin "3") (pinfunction "D_3") (pintype "passive"))
    )
    (net (code "57") (name "Net-(Q6-G)") (class "Default")
      (node (ref "Q6") (pin "1") (pinfunction "G_1") (pintype "passive"))
      (node (ref "R279") (pin "2") (pinfunction "2_2") (pintype "passive"))
      (node (ref "R94") (pin "2") (pinfunction "2_2") (pintype "passive"))
    )
    (net (code "58") (name "Net-(U10-R1{slash}C1_(PU))") (class "Default")
      (node (ref "R280") (pin "1") (pinfunction "1_1") (pintype "passive"))
      (node (ref "U10") (pin "6") (pinfunction "R1/C1_(PU)_6") (pintype "passive"))
    )
    (net (code "59") (name "Net-(U10-R2_(PD))") (class "Default")
      (node (ref "R282") (pin "1") (pinfunction "1_1") (pintype "passive"))
      (node (ref "U10") (pin "1") (pinfunction "R2_(PD)_1") (pintype "passive"))
    )
    (net (code "60") (name "Net-(U31-ON{slash}OFF_(TRIG))") (class "Default")
      (node (ref "R284") (pin "2") (pinfunction "2_2") (pintype "passive"))
      (node (ref "R285") (pin "2") (pinfunction "2_2") (pintype "passive"))
      (node (ref "U31") (pin "5") (pinfunction "ON/OFF_(TRIG)_5") (pintype "passive"))
    )
    (net (code "61") (name "Net-(U31-R1{slash}C1_(PU))") (class "Default")
      (node (ref "R283") (pin "1") (pinfunction "1_1") (pintype "passive"))
      (node (ref "U31") (pin "6") (pinfunction "R1/C1_(PU)_6") (pintype "passive"))
    )
    (net (code "62") (name "Net-(U31-R2_(PD))") (class "Default")
      (node (ref "R286") (pin "1") (pinfunction "1_1") (pintype "passive"))
      (node (ref "U31") (pin "1") (pinfunction "R2_(PD)_1") (pintype "passive"))
    )
  )
)
